# Adafruit_STEMMA_Reflective_Photo_Interru.net
KiCad netlist of a schematic drawn in EAGLE
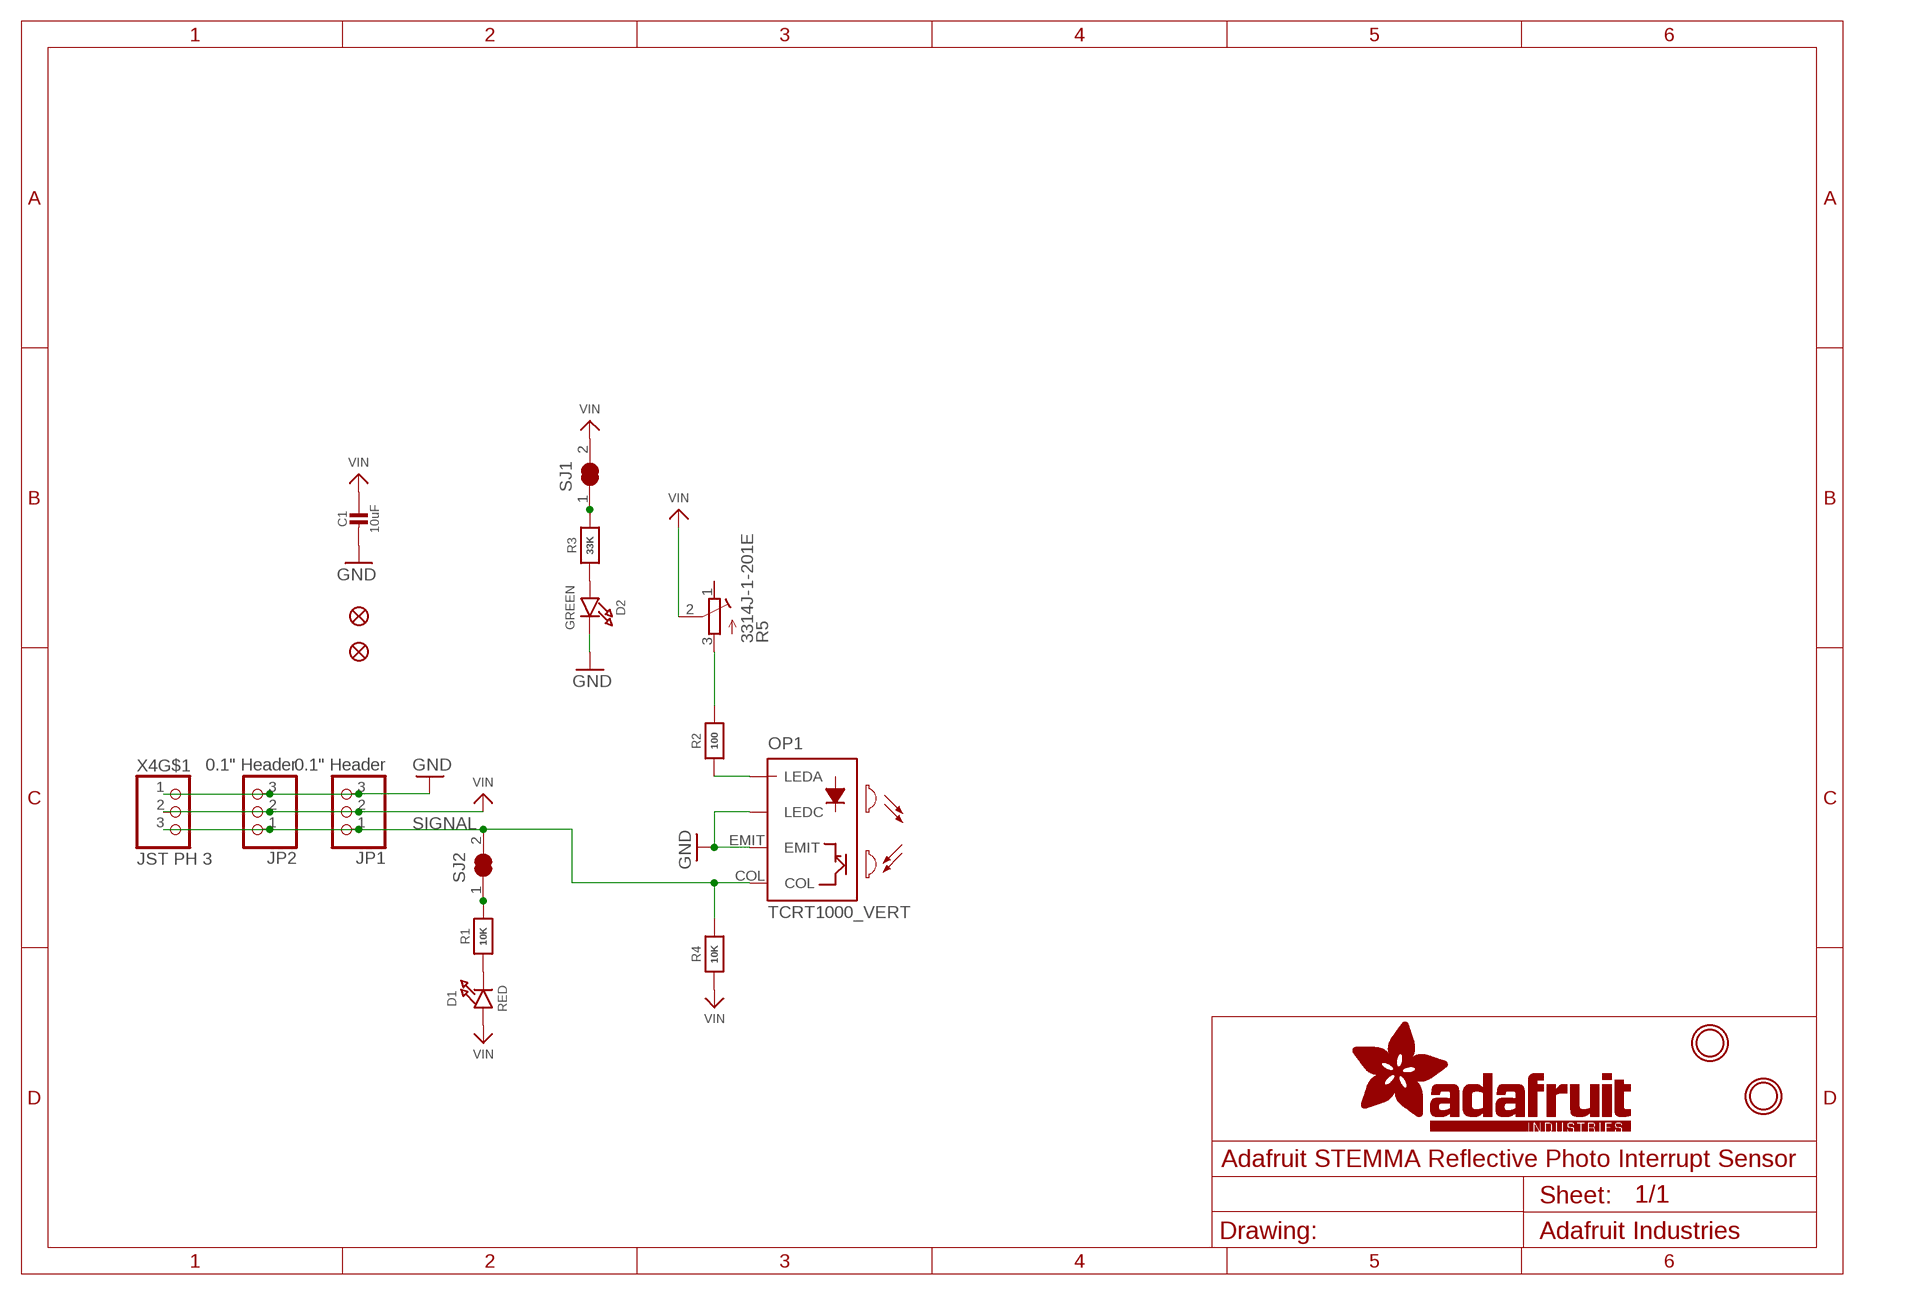
[diagram p0: schematic, sheet 1]

(export (version "E")
  (design (tool "Eeschema 10.0.6"))
  (components
    (comp (ref "C1")
      (value "10uF")
      (footprint "eagle-import:0805-NO")
      (libsource (lib "eagle-import") (part "CAP_CERAMIC0805-NOOUTLINE"))
    )
    (comp (ref "D1")
      (value "RED")
      (footprint "eagle-import:CHIPLED_0603_NOOUTLINE")
      (libsource (lib "eagle-import") (part "LED0603_NOOUTLINE"))
    )
    (comp (ref "D2")
      (value "GREEN")
      (footprint "eagle-import:CHIPLED_0603_NOOUTLINE")
      (libsource (lib "eagle-import") (part "LED0603_NOOUTLINE"))
    )
    (comp (ref "FID2")
      (value "FIDUCIAL_1MM")
      (footprint "eagle-import:FIDUCIAL_1MM")
      (libsource (lib "eagle-import") (part "FIDUCIAL_1MM"))
    )
    (comp (ref "FID3")
      (value "FIDUCIAL_1MM")
      (footprint "eagle-import:FIDUCIAL_1MM")
      (libsource (lib "eagle-import") (part "FIDUCIAL_1MM"))
    )
    (comp (ref "JP1")
      (value "0.1\" Header")
      (footprint "eagle-import:1X03_OVAL")
      (libsource (lib "eagle-import") (part "HEADER-1X3"))
    )
    (comp (ref "JP2")
      (value "0.1\" Header")
      (footprint "eagle-import:1X03_ROUND")
      (libsource (lib "eagle-import") (part "HEADER-1X3ROUND"))
    )
    (comp (ref "OP1")
      (value "TCRT1000_VERT")
      (footprint "eagle-import:TCRT1000")
      (libsource (lib "eagle-import") (part "TCRT1000_VERT"))
    )
    (comp (ref "R1")
      (value "10K")
      (footprint "eagle-import:0603-NO")
      (libsource (lib "eagle-import") (part "RESISTOR_0603_NOOUT"))
    )
    (comp (ref "R2")
      (value "100")
      (footprint "eagle-import:0603-NO")
      (libsource (lib "eagle-import") (part "RESISTOR_0603_NOOUT"))
    )
    (comp (ref "R3")
      (value "33K")
      (footprint "eagle-import:0603-NO")
      (libsource (lib "eagle-import") (part "RESISTOR_0603_NOOUT"))
    )
    (comp (ref "R4")
      (value "10K")
      (footprint "eagle-import:0603-NO")
      (libsource (lib "eagle-import") (part "RESISTOR_0603_NOOUT"))
    )
    (comp (ref "R5")
      (value "3314J-1-201E")
      (footprint "eagle-import:RTRIM3314J")
      (libsource (lib "eagle-import") (part "R-TRIMM3314J"))
    )
    (comp (ref "SJ1")
      (value "SOLDERJUMPER_CLOSED")
      (footprint "eagle-import:SOLDERJUMPER_CLOSEDWIRE")
      (libsource (lib "eagle-import") (part "SOLDERJUMPER_CLOSED"))
    )
    (comp (ref "SJ2")
      (value "SOLDERJUMPER_CLOSED")
      (footprint "eagle-import:SOLDERJUMPER_CLOSEDWIRE")
      (libsource (lib "eagle-import") (part "SOLDERJUMPER_CLOSED"))
    )
    (comp (ref "U$1")
      (value "MOUNTINGHOLE2.5")
      (footprint "eagle-import:MOUNTINGHOLE_2.5_PLATED")
      (libsource (lib "eagle-import") (part "MOUNTINGHOLE2.5"))
    )
    (comp (ref "U$8")
      (value "MOUNTINGHOLE2.5")
      (footprint "eagle-import:MOUNTINGHOLE_2.5_PLATED")
      (libsource (lib "eagle-import") (part "MOUNTINGHOLE2.5"))
    )
    (comp (ref "X4")
      (value "JST PH 3")
      (footprint "eagle-import:JSTPH3")
      (libsource (lib "eagle-import") (part "CON_JST_PH_3PIN"))
    )
  )
  (nets
    (net (code "1") (name "/SIGNAL") (class "Default")
      (node (ref "JP1") (pin "1") (pinfunction "1_1") (pintype "passive"))
      (node (ref "JP2") (pin "1") (pinfunction "1_1") (pintype "passive"))
      (node (ref "OP1") (pin "COL") (pinfunction "COL_COL") (pintype "passive"))
      (node (ref "R4") (pin "2") (pinfunction "2_2") (pintype "passive"))
      (node (ref "SJ2") (pin "2") (pinfunction "2_2") (pintype "passive"))
      (node (ref "X4") (pin "3") (pinfunction "3_3") (pintype "passive"))
    )
    (net (code "2") (name "GND") (class "Default")
      (node (ref "C1") (pin "2") (pinfunction "2_2") (pintype "passive"))
      (node (ref "D2") (pin "C") (pinfunction "C_C") (pintype "passive"))
      (node (ref "JP1") (pin "3") (pinfunction "3_3") (pintype "passive"))
      (node (ref "JP2") (pin "3") (pinfunction "3_3") (pintype "passive"))
      (node (ref "OP1") (pin "EMIT") (pinfunction "EMIT_EMIT") (pintype "passive"))
      (node (ref "OP1") (pin "LEDC") (pinfunction "LEDC_LEDC") (pintype "passive"))
      (node (ref "X4") (pin "1") (pinfunction "1_1") (pintype "passive"))
    )
    (net (code "3") (name "Net-(D1-PadC)") (class "Default")
      (node (ref "D1") (pin "C") (pinfunction "C_C") (pintype "passive"))
      (node (ref "R1") (pin "1") (pinfunction "1_1") (pintype "passive"))
    )
    (net (code "4") (name "Net-(D2-PadA)") (class "Default")
      (node (ref "D2") (pin "A") (pinfunction "A_A") (pintype "passive"))
      (node (ref "R3") (pin "1") (pinfunction "1_1") (pintype "passive"))
    )
    (net (code "5") (name "Net-(OP1-PadLEDA)") (class "Default")
      (node (ref "OP1") (pin "LEDA") (pinfunction "LEDA_LEDA") (pintype "passive"))
      (node (ref "R2") (pin "1") (pinfunction "1_1") (pintype "passive"))
    )
    (net (code "6") (name "Net-(R1-Pad2)") (class "Default")
      (node (ref "R1") (pin "2") (pinfunction "2_2") (pintype "passive"))
      (node (ref "SJ2") (pin "1") (pinfunction "1_1") (pintype "passive"))
    )
    (net (code "7") (name "Net-(R3-Pad2)") (class "Default")
      (node (ref "R3") (pin "2") (pinfunction "2_2") (pintype "passive"))
      (node (ref "SJ1") (pin "1") (pinfunction "1_1") (pintype "passive"))
    )
    (net (code "8") (name "Net-(R5-A)") (class "Default")
      (node (ref "R2") (pin "2") (pinfunction "2_2") (pintype "passive"))
      (node (ref "R5") (pin "3") (pinfunction "A_3") (pintype "passive"))
    )
    (net (code "9") (name "VIN") (class "Default")
      (node (ref "C1") (pin "1") (pinfunction "1_1") (pintype "passive"))
      (node (ref "D1") (pin "A") (pinfunction "A_A") (pintype "passive"))
      (node (ref "JP1") (pin "2") (pinfunction "2_2") (pintype "passive"))
      (node (ref "JP2") (pin "2") (pinfunction "2_2") (pintype "passive"))
      (node (ref "R4") (pin "1") (pinfunction "1_1") (pintype "passive"))
      (node (ref "R5") (pin "2") (pinfunction "S_2") (pintype "passive"))
      (node (ref "SJ1") (pin "2") (pinfunction "2_2") (pintype "passive"))
      (node (ref "X4") (pin "2") (pinfunction "2_2") (pintype "passive"))
    )
    (net (code "10") (name "unconnected-(R5-E-Pad1)") (class "Default")
      (node (ref "R5") (pin "1") (pinfunction "E_1") (pintype "passive"))
    )
  )
)
